# CHIP_tzatziffy_v9.net
KiCad netlist of a schematic drawn in EAGLE
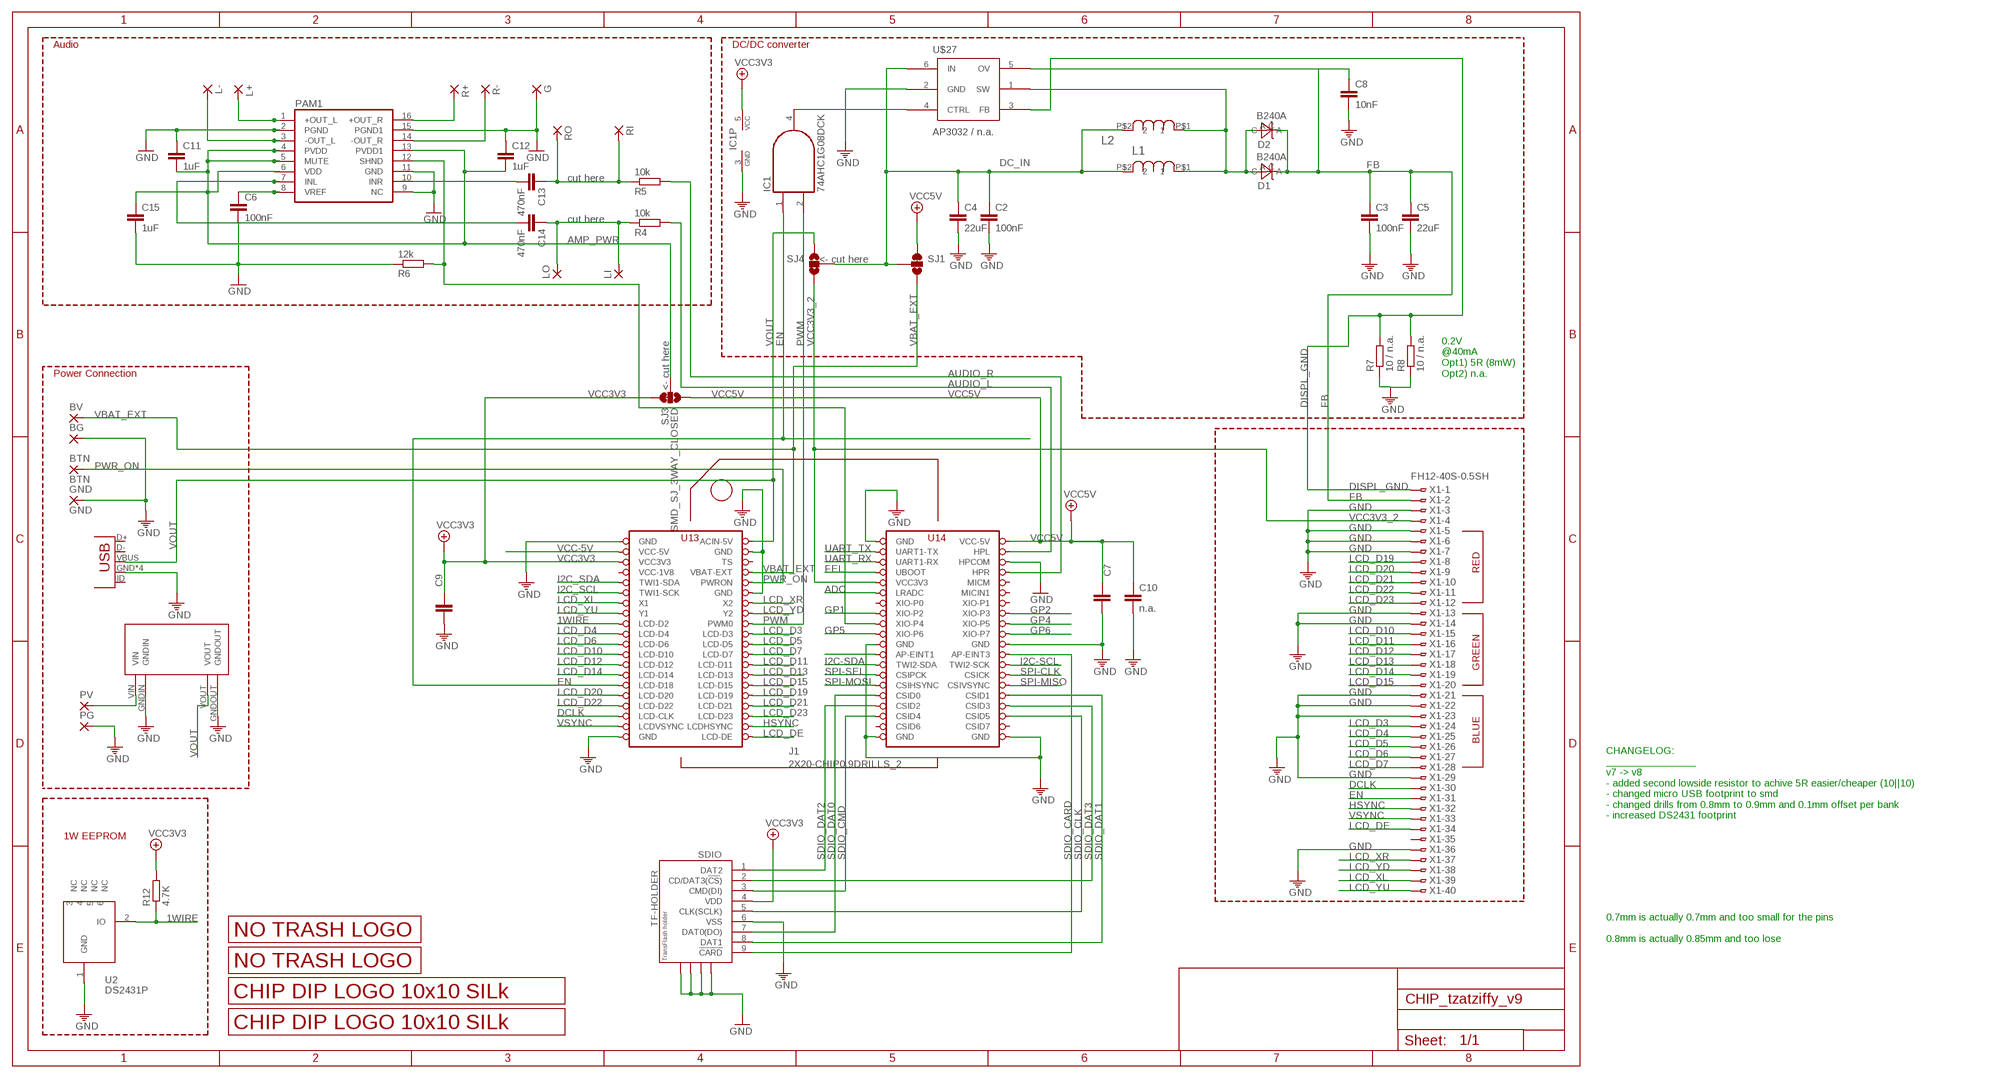
[diagram p0: schematic, sheet 1]

(export (version "E")
  (design (tool "Eeschema 10.0.6"))
  (components
    (comp (ref "BG")
      (value "1,6/0,8")
      (footprint "eagle-import:1,6_0,8")
      (libsource (lib "eagle-import") (part "1,6/0,8"))
    )
    (comp (ref "BTN")
      (value "BTN")
      (footprint "eagle-import:SMD1,27-2,54")
      (libsource (lib "eagle-import") (part "SMD2"))
    )
    (comp (ref "BV")
      (value "1,6/0,8")
      (footprint "eagle-import:1,6_0,8")
      (libsource (lib "eagle-import") (part "1,6/0,8"))
    )
    (comp (ref "C2")
      (value "100nF")
      (footprint "eagle-import:C0805")
      (libsource (lib "eagle-import") (part "C-EUC0805"))
    )
    (comp (ref "C3")
      (value "100nF")
      (footprint "eagle-import:C0805")
      (libsource (lib "eagle-import") (part "C-EUC0805"))
    )
    (comp (ref "C4")
      (value "22uF")
      (footprint "eagle-import:C1206")
      (libsource (lib "eagle-import") (part "C-EUC1206"))
    )
    (comp (ref "C5")
      (value "22uF")
      (footprint "eagle-import:C1206")
      (libsource (lib "eagle-import") (part "C-EUC1206"))
    )
    (comp (ref "C6")
      (value "100nF")
      (footprint "eagle-import:C0805")
      (libsource (lib "eagle-import") (part "C-EUC0805"))
    )
    (comp (ref "C7")
      (value "n.a.")
      (footprint "eagle-import:C0805")
      (libsource (lib "eagle-import") (part "C-EUC0805"))
    )
    (comp (ref "C8")
      (value "10nF")
      (footprint "eagle-import:C0805")
      (libsource (lib "eagle-import") (part "C-EUC0805"))
    )
    (comp (ref "C9")
      (value "n.a.")
      (footprint "eagle-import:C0805")
      (libsource (lib "eagle-import") (part "C-EUC0805"))
    )
    (comp (ref "C10")
      (value "n.a.")
      (footprint "eagle-import:C0805")
      (libsource (lib "eagle-import") (part "C-EUC0805"))
    )
    (comp (ref "C11")
      (value "1uF")
      (footprint "eagle-import:C0805")
      (libsource (lib "eagle-import") (part "C-EUC0805"))
    )
    (comp (ref "C12")
      (value "1uF")
      (footprint "eagle-import:C0805")
      (libsource (lib "eagle-import") (part "C-EUC0805"))
    )
    (comp (ref "C13")
      (value "470nF")
      (footprint "eagle-import:C0805")
      (libsource (lib "eagle-import") (part "C-EUC0805"))
    )
    (comp (ref "C14")
      (value "470nF")
      (footprint "eagle-import:C0805")
      (libsource (lib "eagle-import") (part "C-EUC0805"))
    )
    (comp (ref "C15")
      (value "1uF")
      (footprint "eagle-import:C0805")
      (libsource (lib "eagle-import") (part "C-EUC0805"))
    )
    (comp (ref "D1")
      (value "B240A")
      (footprint "eagle-import:DO-214AC")
      (fields (field (name "MFG") "DIGIKEY") (field (name "VENDOR_PART_NUMBER") "B240A-13-F"))
      (libsource (lib "eagle-import") (part "DIODE_SCHTKY_B240"))
    )
    (comp (ref "D2")
      (value "B240A")
      (footprint "eagle-import:DO-214AC")
      (fields (field (name "MFG") "DIGIKEY") (field (name "VENDOR_PART_NUMBER") "B240A-13-F"))
      (libsource (lib "eagle-import") (part "DIODE_SCHTKY_B240"))
    )
    (comp (ref "G")
      (value "1,6/0,8")
      (footprint "eagle-import:1,6_0,8")
      (libsource (lib "eagle-import") (part "1,6/0,8"))
    )
    (comp (ref "GND")
      (value "GND")
      (footprint "eagle-import:SMD1,27-2,54")
      (libsource (lib "eagle-import") (part "SMD2"))
    )
    (comp (ref "IC1")
      (value "74AHC1G08DCK")
      (footprint "eagle-import:SC70-5")
      (libsource (lib "eagle-import") (part "741G08DCKAHC"))
    )
    (comp (ref "J1")
      (value "2X20-CHIP0.9DRILLS_2")
      (footprint "eagle-import:2X20CHIP_BANK_OFFSET_TH_0.9")
      (libsource (lib "eagle-import") (part "2X20-CHIP0.9DRILLS_2"))
    )
    (comp (ref "JP1")
      (value "USBMICRO_SMD")
      (footprint "eagle-import:USB-B-MICRO-SMD_V03")
      (libsource (lib "eagle-import") (part "USBMICRO_SMD"))
    )
    (comp (ref "L+")
      (value "1,6/0,8")
      (footprint "eagle-import:1,6_0,8")
      (libsource (lib "eagle-import") (part "1,6/0,8"))
    )
    (comp (ref "L-")
      (value "1,6/0,8")
      (footprint "eagle-import:1,6_0,8")
      (libsource (lib "eagle-import") (part "1,6/0,8"))
    )
    (comp (ref "L1")
      (value "SRN6045-100M")
      (footprint "eagle-import:SRN6045")
      (fields (field (name "MFG") "DIGIKEY"))
      (libsource (lib "eagle-import") (part "SRN6045-100M"))
    )
    (comp (ref "L2")
      (value "SRN6045-100M")
      (footprint "eagle-import:SRN6045")
      (fields (field (name "MFG") "DIGIKEY"))
      (libsource (lib "eagle-import") (part "SRN6045-100M"))
    )
    (comp (ref "LI")
      (value "1,6/0,8")
      (footprint "eagle-import:1,6_0,8")
      (libsource (lib "eagle-import") (part "1,6/0,8"))
    )
    (comp (ref "LO")
      (value "1,6/0,8")
      (footprint "eagle-import:1,6_0,8")
      (libsource (lib "eagle-import") (part "1,6/0,8"))
    )
    (comp (ref "PAM1")
      (value "PAM8403")
      (footprint "eagle-import:SOP-16")
      (libsource (lib "eagle-import") (part "PAM8403"))
    )
    (comp (ref "PG")
      (value "1,6/0,8")
      (footprint "eagle-import:1,6_0,8")
      (libsource (lib "eagle-import") (part "1,6/0,8"))
    )
    (comp (ref "PV")
      (value "1,6/0,8")
      (footprint "eagle-import:1,6_0,8")
      (libsource (lib "eagle-import") (part "1,6/0,8"))
    )
    (comp (ref "R+")
      (value "1,6/0,8")
      (footprint "eagle-import:1,6_0,8")
      (libsource (lib "eagle-import") (part "1,6/0,8"))
    )
    (comp (ref "R-")
      (value "1,6/0,8")
      (footprint "eagle-import:1,6_0,8")
      (libsource (lib "eagle-import") (part "1,6/0,8"))
    )
    (comp (ref "R4")
      (value "10k")
      (footprint "eagle-import:R0805")
      (libsource (lib "eagle-import") (part "R-EU_R0805"))
    )
    (comp (ref "R5")
      (value "10k")
      (footprint "eagle-import:R0805")
      (libsource (lib "eagle-import") (part "R-EU_R0805"))
    )
    (comp (ref "R6")
      (value "12k")
      (footprint "eagle-import:R0805")
      (libsource (lib "eagle-import") (part "R-EU_R0805"))
    )
    (comp (ref "R7")
      (value "10 / n.a.")
      (footprint "eagle-import:M0805")
      (libsource (lib "eagle-import") (part "R-EU_M0805"))
    )
    (comp (ref "R8")
      (value "10 / n.a.")
      (footprint "eagle-import:M0805")
      (libsource (lib "eagle-import") (part "R-EU_M0805"))
    )
    (comp (ref "R12")
      (value "4.7K")
      (footprint "eagle-import:M0805")
      (libsource (lib "eagle-import") (part "R-EU_M0805"))
    )
    (comp (ref "RI")
      (value "1,6/0,8")
      (footprint "eagle-import:1,6_0,8")
      (libsource (lib "eagle-import") (part "1,6/0,8"))
    )
    (comp (ref "RO")
      (value "1,6/0,8")
      (footprint "eagle-import:1,6_0,8")
      (libsource (lib "eagle-import") (part "1,6/0,8"))
    )
    (comp (ref "SDIO")
      (value "TF-HOLDER")
      (footprint "eagle-import:TF-PULL")
      (libsource (lib "eagle-import") (part "TF-HOLDER"))
    )
    (comp (ref "SJ1")
      (value "SMD_SJ_3WAY_CLOSED")
      (footprint "eagle-import:SMD_SJ_3WAY_CLOSED")
      (libsource (lib "eagle-import") (part "SMD_SJ_3WAY_CLOSED"))
    )
    (comp (ref "SJ3")
      (value "SMD_SJ_3WAY_CLOSED")
      (footprint "eagle-import:SMD_SJ_3WAY_CLOSED")
      (libsource (lib "eagle-import") (part "SMD_SJ_3WAY_CLOSED"))
    )
    (comp (ref "SJ4")
      (value "SMD_SJ_3WAY_OPENT")
      (footprint "eagle-import:SMD_SJ_3WAY_OPEN")
      (libsource (lib "eagle-import") (part "SMD_SJ_3WAY_OPENT"))
    )
    (comp (ref "U$2")
      (value "LOGO_10X10_SILK")
      (footprint "eagle-import:LOGO2_10X10_SILK")
      (libsource (lib "eagle-import") (part "LOGO_10X10_SILK"))
    )
    (comp (ref "U$3")
      (value "LOGO_NO_TRASHROHS")
      (footprint "eagle-import:LOGO_ROHS_SYM")
      (libsource (lib "eagle-import") (part "LOGO_NO_TRASHROHS"))
    )
    (comp (ref "U$4")
      (value "LOGO_NO_TRASHNO_TRASH")
      (footprint "eagle-import:LOGO_ROHS_NO_TRASH")
      (libsource (lib "eagle-import") (part "LOGO_NO_TRASHNO_TRASH"))
    )
    (comp (ref "U$5")
      (value "LOGO_10X10_SILK")
      (footprint "eagle-import:LOGO2_10X10_SILK")
      (libsource (lib "eagle-import") (part "LOGO_10X10_SILK"))
    )
    (comp (ref "U$10")
      (value "MP1584EN_FRAMELESS")
      (footprint "eagle-import:MP1584EN_FRAMELESS")
      (libsource (lib "eagle-import") (part "MP1584EN_FRAMELESS"))
    )
    (comp (ref "U$27")
      (value "AP3032 / n.a.")
      (footprint "eagle-import:SOT23-6")
      (libsource (lib "eagle-import") (part "AP3032"))
    )
    (comp (ref "U2")
      (value "DS2431P")
      (footprint "eagle-import:TSOC6")
      (fields (field (name "MFG") "DIGIKEY") (field (name "VENDOR_PART_NUMBER") "DS2431P+T&R"))
      (libsource (lib "eagle-import") (part "DS2431P"))
    )
    (comp (ref "X1")
      (value "FH12-40S-0.5SH")
      (footprint "eagle-import:FH12-40S-0.5SH")
      (fields (field (name "MFG") "DIGIKEY") (field (name "VENDOR_PART_NUMBER") "FH12-40S-0.5SH(55)"))
      (libsource (lib "eagle-import") (part "FH12-40S-0.5SH"))
    )
  )
  (nets
    (net (code "1") (name "/1WIRE") (class "Default")
      (node (ref "J1") (pin "LCD-D2") (pinfunction "LCD-D2_LCD-D2") (pintype "passive"))
      (node (ref "R12") (pin "1") (pinfunction "1_1") (pintype "passive"))
      (node (ref "U2") (pin "2") (pinfunction "IO_2") (pintype "bidirectional"))
    )
    (net (code "2") (name "/ADC") (class "Default")
      (node (ref "J1") (pin "LRADC") (pinfunction "LRADC_LRADC") (pintype "passive"))
    )
    (net (code "3") (name "/AMP_PWR") (class "Default")
      (node (ref "C11") (pin "2") (pinfunction "2_2") (pintype "passive"))
      (node (ref "C12") (pin "2") (pinfunction "2_2") (pintype "passive"))
      (node (ref "C15") (pin "1") (pinfunction "1_1") (pintype "passive"))
      (node (ref "PAM1") (pin "13") (pinfunction "PVDD1_13") (pintype "output"))
      (node (ref "PAM1") (pin "4") (pinfunction "PVDD_4") (pintype "input"))
      (node (ref "PAM1") (pin "5") (pinfunction "MUTE_5") (pintype "input"))
      (node (ref "PAM1") (pin "6") (pinfunction "VDD_6") (pintype "input"))
      (node (ref "SJ3") (pin "2") (pinfunction "2_2") (pintype "passive"))
    )
    (net (code "4") (name "/AUDIO_L") (class "Default")
      (node (ref "J1") (pin "HPL") (pinfunction "HPL_HPL") (pintype "passive"))
      (node (ref "R4") (pin "2") (pinfunction "2_2") (pintype "passive"))
    )
    (net (code "5") (name "/AUDIO_R") (class "Default")
      (node (ref "J1") (pin "HPR") (pinfunction "HPR_HPR") (pintype "passive"))
      (node (ref "R5") (pin "2") (pinfunction "2_2") (pintype "passive"))
    )
    (net (code "6") (name "/DCLK") (class "Default")
      (node (ref "J1") (pin "LCD-CLK") (pinfunction "LCD-CLK_LCD-CLK") (pintype "passive"))
      (node (ref "X1") (pin "30") (pinfunction "1_30") (pintype "passive"))
    )
    (net (code "7") (name "/DC_IN") (class "Default")
      (node (ref "C2") (pin "1") (pinfunction "1_1") (pintype "passive"))
      (node (ref "C4") (pin "1") (pinfunction "1_1") (pintype "passive"))
      (node (ref "L1") (pin "P$2") (pinfunction "2_P$2") (pintype "passive"))
      (node (ref "L2") (pin "P$2") (pinfunction "2_P$2") (pintype "passive"))
      (node (ref "SJ1") (pin "2") (pinfunction "2_2") (pintype "passive"))
      (node (ref "SJ4") (pin "2") (pinfunction "2_2") (pintype "passive"))
      (node (ref "U$27") (pin "6") (pinfunction "IN_6") (pintype "power_in"))
    )
    (net (code "8") (name "/DISPL_GND") (class "Default")
      (node (ref "R7") (pin "2") (pinfunction "2_2") (pintype "passive"))
      (node (ref "R8") (pin "2") (pinfunction "2_2") (pintype "passive"))
      (node (ref "U$27") (pin "3") (pinfunction "FB_3") (pintype "passive"))
      (node (ref "X1") (pin "1") (pinfunction "1_1") (pintype "passive"))
    )
    (net (code "9") (name "/EN") (class "Default")
      (node (ref "IC1") (pin "1") (pinfunction "I0_1") (pintype "input"))
      (node (ref "J1") (pin "LCD-D18") (pinfunction "LCD-D18_LCD-D18") (pintype "passive"))
      (node (ref "X1") (pin "31") (pinfunction "1_31") (pintype "passive"))
    )
    (net (code "10") (name "/FB") (class "Default")
      (node (ref "C3") (pin "1") (pinfunction "1_1") (pintype "passive"))
      (node (ref "C5") (pin "1") (pinfunction "1_1") (pintype "passive"))
      (node (ref "C8") (pin "1") (pinfunction "1_1") (pintype "passive"))
      (node (ref "D1") (pin "C") (pinfunction "C_C") (pintype "bidirectional"))
      (node (ref "D2") (pin "C") (pinfunction "C_C") (pintype "bidirectional"))
      (node (ref "U$27") (pin "5") (pinfunction "OV_5") (pintype "power_in"))
      (node (ref "X1") (pin "2") (pinfunction "1_2") (pintype "passive"))
    )
    (net (code "11") (name "/FEL") (class "Default")
      (node (ref "J1") (pin "FEL") (pinfunction "UBOOT_FEL") (pintype "passive"))
    )
    (net (code "12") (name "/GP1") (class "Default")
      (node (ref "J1") (pin "XIO-P2") (pinfunction "XIO-P2_XIO-P2") (pintype "passive"))
    )
    (net (code "13") (name "/GP2") (class "Default")
      (node (ref "J1") (pin "XIO-P3") (pinfunction "XIO-P3_XIO-P3") (pintype "passive"))
    )
    (net (code "14") (name "/GP4") (class "Default")
      (node (ref "J1") (pin "XIO-P5") (pinfunction "XIO-P5_XIO-P5") (pintype "passive"))
    )
    (net (code "15") (name "/GP5") (class "Default")
      (node (ref "J1") (pin "XIO-P6") (pinfunction "XIO-P6_XIO-P6") (pintype "passive"))
    )
    (net (code "16") (name "/GP6") (class "Default")
      (node (ref "J1") (pin "XIO-P7") (pinfunction "XIO-P7_XIO-P7") (pintype "passive"))
    )
    (net (code "17") (name "/HSYNC") (class "Default")
      (node (ref "J1") (pin "LCD-HSYNC") (pinfunction "LCDHSYNC_LCD-HSYNC") (pintype "passive"))
      (node (ref "X1") (pin "32") (pinfunction "1_32") (pintype "passive"))
    )
    (net (code "18") (name "/I2C-SCL") (class "Default")
      (node (ref "J1") (pin "TWI2-SCK") (pinfunction "TWI2-SCK_TWI2-SCK") (pintype "passive"))
    )
    (net (code "19") (name "/I2C-SDA") (class "Default")
      (node (ref "J1") (pin "TWI2-SDA") (pinfunction "TWI2-SDA_TWI2-SDA") (pintype "passive"))
    )
    (net (code "20") (name "/I2C_SCL") (class "Default")
      (node (ref "J1") (pin "TWI1-SCK") (pinfunction "TWI1-SCK_TWI1-SCK") (pintype "passive"))
    )
    (net (code "21") (name "/I2C_SDA") (class "Default")
      (node (ref "J1") (pin "TWI1-SDA") (pinfunction "TWI1-SDA_TWI1-SDA") (pintype "passive"))
    )
    (net (code "22") (name "/LCD_D3") (class "Default")
      (node (ref "J1") (pin "LCD-D3") (pinfunction "LCD-D3_LCD-D3") (pintype "passive"))
      (node (ref "X1") (pin "24") (pinfunction "1_24") (pintype "passive"))
    )
    (net (code "23") (name "/LCD_D4") (class "Default")
      (node (ref "J1") (pin "LCD-D4") (pinfunction "LCD-D4_LCD-D4") (pintype "passive"))
      (node (ref "X1") (pin "25") (pinfunction "1_25") (pintype "passive"))
    )
    (net (code "24") (name "/LCD_D5") (class "Default")
      (node (ref "J1") (pin "LCD-D5") (pinfunction "LCD-D5_LCD-D5") (pintype "passive"))
      (node (ref "X1") (pin "26") (pinfunction "1_26") (pintype "passive"))
    )
    (net (code "25") (name "/LCD_D6") (class "Default")
      (node (ref "J1") (pin "LCD-D6") (pinfunction "LCD-D6_LCD-D6") (pintype "passive"))
      (node (ref "X1") (pin "27") (pinfunction "1_27") (pintype "passive"))
    )
    (net (code "26") (name "/LCD_D7") (class "Default")
      (node (ref "J1") (pin "LCD-D7") (pinfunction "LCD-D7_LCD-D7") (pintype "passive"))
      (node (ref "X1") (pin "28") (pinfunction "1_28") (pintype "passive"))
    )
    (net (code "27") (name "/LCD_D10") (class "Default")
      (node (ref "J1") (pin "LCD-D10") (pinfunction "LCD-D10_LCD-D10") (pintype "passive"))
      (node (ref "X1") (pin "15") (pinfunction "1_15") (pintype "passive"))
    )
    (net (code "28") (name "/LCD_D11") (class "Default")
      (node (ref "J1") (pin "LCD-D11") (pinfunction "LCD-D11_LCD-D11") (pintype "passive"))
      (node (ref "X1") (pin "16") (pinfunction "1_16") (pintype "passive"))
    )
    (net (code "29") (name "/LCD_D12") (class "Default")
      (node (ref "J1") (pin "LCD-D12") (pinfunction "LCD-D12_LCD-D12") (pintype "passive"))
      (node (ref "X1") (pin "17") (pinfunction "1_17") (pintype "passive"))
    )
    (net (code "30") (name "/LCD_D13") (class "Default")
      (node (ref "J1") (pin "LCD-D13") (pinfunction "LCD-D13_LCD-D13") (pintype "passive"))
      (node (ref "X1") (pin "18") (pinfunction "1_18") (pintype "passive"))
    )
    (net (code "31") (name "/LCD_D14") (class "Default")
      (node (ref "J1") (pin "LCD-D14") (pinfunction "LCD-D14_LCD-D14") (pintype "passive"))
      (node (ref "X1") (pin "19") (pinfunction "1_19") (pintype "passive"))
    )
    (net (code "32") (name "/LCD_D15") (class "Default")
      (node (ref "J1") (pin "LCD-D15") (pinfunction "LCD-D15_LCD-D15") (pintype "passive"))
      (node (ref "X1") (pin "20") (pinfunction "1_20") (pintype "passive"))
    )
    (net (code "33") (name "/LCD_D19") (class "Default")
      (node (ref "J1") (pin "LCD-D19") (pinfunction "LCD-D19_LCD-D19") (pintype "passive"))
      (node (ref "X1") (pin "8") (pinfunction "1_8") (pintype "passive"))
    )
    (net (code "34") (name "/LCD_D20") (class "Default")
      (node (ref "J1") (pin "LCD-D20") (pinfunction "LCD-D20_LCD-D20") (pintype "passive"))
      (node (ref "X1") (pin "9") (pinfunction "1_9") (pintype "passive"))
    )
    (net (code "35") (name "/LCD_D21") (class "Default")
      (node (ref "J1") (pin "LCD-D21") (pinfunction "LCD-D21_LCD-D21") (pintype "passive"))
      (node (ref "X1") (pin "10") (pinfunction "1_10") (pintype "passive"))
    )
    (net (code "36") (name "/LCD_D22") (class "Default")
      (node (ref "J1") (pin "LCD-D22") (pinfunction "LCD-D22_LCD-D22") (pintype "passive"))
      (node (ref "X1") (pin "11") (pinfunction "1_11") (pintype "passive"))
    )
    (net (code "37") (name "/LCD_D23") (class "Default")
      (node (ref "J1") (pin "LCD-D23") (pinfunction "LCD-D23_LCD-D23") (pintype "passive"))
      (node (ref "X1") (pin "12") (pinfunction "1_12") (pintype "passive"))
    )
    (net (code "38") (name "/LCD_DE") (class "Default")
      (node (ref "J1") (pin "LCD-DE") (pinfunction "LCD-DE_LCD-DE") (pintype "passive"))
      (node (ref "X1") (pin "34") (pinfunction "1_34") (pintype "passive"))
    )
    (net (code "39") (name "/LCD_XL") (class "Default")
      (node (ref "J1") (pin "X1") (pinfunction "X1_X1") (pintype "passive"))
      (node (ref "X1") (pin "39") (pinfunction "1_39") (pintype "passive"))
    )
    (net (code "40") (name "/LCD_XR") (class "Default")
      (node (ref "J1") (pin "X2") (pinfunction "X2_X2") (pintype "passive"))
      (node (ref "X1") (pin "37") (pinfunction "1_37") (pintype "passive"))
    )
    (net (code "41") (name "/LCD_YD") (class "Default")
      (node (ref "J1") (pin "Y2") (pinfunction "Y2_Y2") (pintype "passive"))
      (node (ref "X1") (pin "38") (pinfunction "1_38") (pintype "passive"))
    )
    (net (code "42") (name "/LCD_YU") (class "Default")
      (node (ref "J1") (pin "Y1") (pinfunction "Y1_Y1") (pintype "passive"))
      (node (ref "X1") (pin "40") (pinfunction "1_40") (pintype "passive"))
    )
    (net (code "43") (name "/PWM") (class "Default")
      (node (ref "IC1") (pin "2") (pinfunction "I1_2") (pintype "input"))
      (node (ref "J1") (pin "PWM0") (pinfunction "PWM0_PWM0") (pintype "passive"))
    )
    (net (code "44") (name "/PWR_ON") (class "Default")
      (node (ref "BTN") (pin "1") (pinfunction "P_1") (pintype "passive"))
      (node (ref "J1") (pin "PWRON") (pinfunction "PWRON_PWRON") (pintype "passive"))
    )
    (net (code "45") (name "/SDIO_CARD") (class "Default")
      (node (ref "J1") (pin "AP-EINT3") (pinfunction "AP-EINT3_AP-EINT3") (pintype "passive"))
      (node (ref "SDIO") (pin "9") (pinfunction "~{CARD}_9") (pintype "passive"))
    )
    (net (code "46") (name "/SDIO_CLK") (class "Default")
      (node (ref "J1") (pin "CSID5") (pinfunction "CSID5_CSID5") (pintype "passive"))
      (node (ref "SDIO") (pin "5") (pinfunction "CLK(SCLK)_5") (pintype "input"))
    )
    (net (code "47") (name "/SDIO_CMD") (class "Default")
      (node (ref "J1") (pin "CSID4") (pinfunction "CSID4_CSID4") (pintype "passive"))
      (node (ref "SDIO") (pin "3") (pinfunction "CMD(DI)_3") (pintype "bidirectional"))
    )
    (net (code "48") (name "/SDIO_DAT0") (class "Default")
      (node (ref "J1") (pin "CSID0") (pinfunction "CSID0_CSID0") (pintype "passive"))
      (node (ref "SDIO") (pin "7") (pinfunction "DAT0(DO)_7") (pintype "bidirectional"))
    )
    (net (code "49") (name "/SDIO_DAT1") (class "Default")
      (node (ref "J1") (pin "CSID1") (pinfunction "CSID1_CSID1") (pintype "passive"))
      (node (ref "SDIO") (pin "8") (pinfunction "DAT1_8") (pintype "bidirectional"))
    )
    (net (code "50") (name "/SDIO_DAT2") (class "Default")
      (node (ref "J1") (pin "CSID2") (pinfunction "CSID2_CSID2") (pintype "passive"))
      (node (ref "SDIO") (pin "1") (pinfunction "DAT2_1") (pintype "bidirectional"))
    )
    (net (code "51") (name "/SDIO_DAT3") (class "Default")
      (node (ref "J1") (pin "CSID3") (pinfunction "CSID3_CSID3") (pintype "passive"))
      (node (ref "SDIO") (pin "2") (pinfunction "CD/DAT3(~{CS})_2") (pintype "bidirectional"))
    )
    (net (code "52") (name "/SPI-CLK") (class "Default")
      (node (ref "J1") (pin "CSICK") (pinfunction "CSICK_CSICK") (pintype "passive"))
    )
    (net (code "53") (name "/SPI-MISO") (class "Default")
      (node (ref "J1") (pin "CSIVSYNC") (pinfunction "CSIVSYNC_CSIVSYNC") (pintype "passive"))
    )
    (net (code "54") (name "/SPI-MOSI") (class "Default")
      (node (ref "J1") (pin "CSIHSYNC") (pinfunction "CSIHSYNC_CSIHSYNC") (pintype "passive"))
    )
    (net (code "55") (name "/SPI-SEL") (class "Default")
      (node (ref "J1") (pin "CSIPCK") (pinfunction "CSIPCK_CSIPCK") (pintype "passive"))
    )
    (net (code "56") (name "/UART_RX") (class "Default")
      (node (ref "J1") (pin "UART1-RX") (pinfunction "UART1-RX_UART1-RX") (pintype "passive"))
    )
    (net (code "57") (name "/UART_TX") (class "Default")
      (node (ref "J1") (pin "UART1-TX") (pinfunction "UART1-TX_UART1-TX") (pintype "passive"))
    )
    (net (code "58") (name "/VBAT_EXT") (class "Default")
      (node (ref "BV") (pin "1") (pinfunction "P_1") (pintype "passive"))
      (node (ref "J1") (pin "BAT") (pinfunction "VBAT-EXT_BAT") (pintype "passive"))
      (node (ref "SJ1") (pin "3") (pinfunction "3_3") (pintype "passive"))
    )
    (net (code "59") (name "/VCC-1V8") (class "Default")
      (node (ref "J1") (pin "VCC1V8") (pinfunction "VCC-1V8_VCC1V8") (pintype "power_in"))
    )
    (net (code "60") (name "/VCC-5V") (class "Default")
      (node (ref "J1") (pin "VCC5V@0") (pinfunction "VCC-5V_VCC5V@0") (pintype "power_in"))
    )
    (net (code "61") (name "/VCC3V3_2") (class "Default")
      (node (ref "J1") (pin "VCC3V3@1") (pinfunction "VCC3V3_VCC3V3@1") (pintype "power_in"))
      (node (ref "SJ4") (pin "3") (pinfunction "3_3") (pintype "passive"))
      (node (ref "X1") (pin "4") (pinfunction "1_4") (pintype "passive"))
    )
    (net (code "62") (name "/VOUT") (class "Default")
      (node (ref "J1") (pin "CHG-IN") (pinfunction "ACIN-5V_CHG-IN") (pintype "passive"))
      (node (ref "JP1") (pin "VBUS") (pinfunction "VBUS_VBUS") (pintype "bidirectional"))
      (node (ref "SJ4") (pin "1") (pinfunction "1_1") (pintype "passive"))
      (node (ref "U$10") (pin "VOUT") (pinfunction "VOUT_VOUT") (pintype "power_in"))
    )
    (net (code "63") (name "/VSYNC") (class "Default")
      (node (ref "J1") (pin "LCD-VSYNC") (pinfunction "LCDVSYNC_LCD-VSYNC") (pintype "passive"))
      (node (ref "X1") (pin "33") (pinfunction "1_33") (pintype "passive"))
    )
    (net (code "64") (name "GND") (class "Default")
      (node (ref "BG") (pin "1") (pinfunction "P_1") (pintype "passive"))
      (node (ref "C10") (pin "2") (pinfunction "2_2") (pintype "passive"))
      (node (ref "C11") (pin "1") (pinfunction "1_1") (pintype "passive"))
      (node (ref "C12") (pin "1") (pinfunction "1_1") (pintype "passive"))
      (node (ref "C15") (pin "2") (pinfunction "2_2") (pintype "passive"))
      (node (ref "C2") (pin "2") (pinfunction "2_2") (pintype "passive"))
      (node (ref "C3") (pin "2") (pinfunction "2_2") (pintype "passive"))
      (node (ref "C4") (pin "2") (pinfunction "2_2") (pintype "passive"))
      (node (ref "C5") (pin "2") (pinfunction "2_2") (pintype "passive"))
      (node (ref "C6") (pin "2") (pinfunction "2_2") (pintype "passive"))
      (node (ref "C7") (pin "2") (pinfunction "2_2") (pintype "passive"))
      (node (ref "C8") (pin "2") (pinfunction "2_2") (pintype "passive"))
      (node (ref "C9") (pin "2") (pinfunction "2_2") (pintype "passive"))
      (node (ref "G") (pin "1") (pinfunction "P_1") (pintype "passive"))
      (node (ref "GND") (pin "1") (pinfunction "P_1") (pintype "passive"))
      (node (ref "IC1") (pin "3") (pinfunction "GND_3") (pintype "power_in"))
      (node (ref "J1") (pin "GND@1") (pinfunction "GND_GND@1") (pintype "power_in"))
      (node (ref "J1") (pin "GND@10") (pinfunction "GND_GND@10") (pintype "power_in"))
      (node (ref "J1") (pin "GND@2") (pinfunction "GND_GND@2") (pintype "power_in"))
      (node (ref "J1") (pin "GND@3") (pinfunction "GND_GND@3") (pintype "power_in"))
      (node (ref "J1") (pin "GND@4") (pinfunction "GND_GND@4") (pintype "power_in"))
      (node (ref "J1") (pin "GND@5") (pinfunction "GND_GND@5") (pintype "power_in"))
      (node (ref "J1") (pin "GND@6") (pinfunction "GND_GND@6") (pintype "power_in"))
      (node (ref "J1") (pin "GND@7") (pinfunction "GND_GND@7") (pintype "power_in"))
      (node (ref "J1") (pin "GND@8") (pinfunction "GND_GND@8") (pintype "power_in"))
      (node (ref "J1") (pin "HPCOM") (pinfunction "HPCOM_HPCOM") (pintype "passive"))
      (node (ref "JP1") (pin "GND") (pinfunction "GND_GND") (pintype "bidirectional"))
      (node (ref "JP1") (pin "SHIELD1") (pinfunction "GND_SHIELD1") (pintype "bidirectional"))
      (node (ref "JP1") (pin "SHIELD2") (pinfunction "GND_SHIELD2") (pintype "bidirectional"))
      (node (ref "JP1") (pin "SHIELD3") (pinfunction "GND_SHIELD3") (pintype "bidirectional"))
      (node (ref "PAM1") (pin "11") (pinfunction "GND_11") (pintype "output"))
      (node (ref "PAM1") (pin "15") (pinfunction "PGND1_15") (pintype "output"))
      (node (ref "PAM1") (pin "2") (pinfunction "PGND_2") (pintype "input"))
      (node (ref "PAM1") (pin "9") (pinfunction "NC_9") (pintype "output"))
      (node (ref "PG") (pin "1") (pinfunction "P_1") (pintype "passive"))
      (node (ref "R6") (pin "1") (pinfunction "1_1") (pintype "passive"))
      (node (ref "R7") (pin "1") (pinfunction "1_1") (pintype "passive"))
      (node (ref "R8") (pin "1") (pinfunction "1_1") (pintype "passive"))
      (node (ref "SDIO") (pin "6") (pinfunction "VSS_6") (pintype "power_in"))
      (node (ref "SDIO") (pin "S1") (pinfunction "S1_S1") (pintype "passive"))
      (node (ref "SDIO") (pin "S2") (pinfunction "S2_S2") (pintype "passive"))
      (node (ref "SDIO") (pin "S3") (pinfunction "S3_S3") (pintype "passive"))
      (node (ref "SDIO") (pin "S4") (pinfunction "S4_S4") (pintype "passive"))
      (node (ref "U$10") (pin "GNDIN") (pinfunction "GNDIN_GNDIN") (pintype "power_in"))
      (node (ref "U$10") (pin "GNDOUT") (pinfunction "GNDOUT_GNDOUT") (pintype "power_in"))
      (node (ref "U$27") (pin "2") (pinfunction "GND_2") (pintype "power_in"))
      (node (ref "U2") (pin "1") (pinfunction "GND_1") (pintype "bidirectional"))
      (node (ref "X1") (pin "13") (pinfunction "1_13") (pintype "passive"))
      (node (ref "X1") (pin "14") (pinfunction "1_14") (pintype "passive"))
      (node (ref "X1") (pin "21") (pinfunction "1_21") (pintype "passive"))
      (node (ref "X1") (pin "22") (pinfunction "1_22") (pintype "passive"))
      (node (ref "X1") (pin "23") (pinfunction "1_23") (pintype "passive"))
      (node (ref "X1") (pin "29") (pinfunction "1_29") (pintype "passive"))
      (node (ref "X1") (pin "3") (pinfunction "1_3") (pintype "passive"))
      (node (ref "X1") (pin "36") (pinfunction "1_36") (pintype "passive"))
      (node (ref "X1") (pin "5") (pinfunction "1_5") (pintype "passive"))
      (node (ref "X1") (pin "6") (pinfunction "1_6") (pintype "passive"))
      (node (ref "X1") (pin "7") (pinfunction "1_7") (pintype "passive"))
    )
    (net (code "65") (name "Net-(IC1A-O)") (class "Default")
      (node (ref "IC1") (pin "4") (pinfunction "O_4") (pintype "output"))
      (node (ref "U$27") (pin "4") (pinfunction "CTRL_4") (pintype "input"))
    )
    (net (code "66") (name "Net-(L+-P)") (class "Default")
      (node (ref "L+") (pin "1") (pinfunction "P_1") (pintype "passive"))
      (node (ref "PAM1") (pin "1") (pinfunction "+OUT_L_1") (pintype "input"))
    )
    (net (code "67") (name "Net-(L--P)") (class "Default")
      (node (ref "L-") (pin "1") (pinfunction "P_1") (pintype "passive"))
      (node (ref "PAM1") (pin "3") (pinfunction "-OUT_L_3") (pintype "input"))
    )
    (net (code "68") (name "Net-(L1-1)") (class "Default")
      (node (ref "D1") (pin "A") (pinfunction "A_A") (pintype "bidirectional"))
      (node (ref "D2") (pin "A") (pinfunction "A_A") (pintype "bidirectional"))
      (node (ref "L1") (pin "P$1") (pinfunction "1_P$1") (pintype "passive"))
      (node (ref "L2") (pin "P$1") (pinfunction "1_P$1") (pintype "passive"))
      (node (ref "U$27") (pin "1") (pinfunction "SW_1") (pintype "power_in"))
    )
    (net (code "69") (name "Net-(LI-P)") (class "Default")
      (node (ref "C14") (pin "1") (pinfunction "1_1") (pintype "passive"))
      (node (ref "LI") (pin "1") (pinfunction "P_1") (pintype "passive"))
      (node (ref "LO") (pin "1") (pinfunction "P_1") (pintype "passive"))
      (node (ref "R4") (pin "1") (pinfunction "1_1") (pintype "passive"))
    )
    (net (code "70") (name "Net-(PAM1-+OUT_R)") (class "Default")
      (node (ref "PAM1") (pin "16") (pinfunction "+OUT_R_16") (pintype "output"))
      (node (ref "R+") (pin "1") (pinfunction "P_1") (pintype "passive"))
    )
    (net (code "71") (name "Net-(PAM1--OUT_R)") (class "Default")
      (node (ref "PAM1") (pin "14") (pinfunction "-OUT_R_14") (pintype "output"))
      (node (ref "R-") (pin "1") (pinfunction "P_1") (pintype "passive"))
    )
    (net (code "72") (name "Net-(PAM1-INL)") (class "Default")
      (node (ref "C14") (pin "2") (pinfunction "2_2") (pintype "passive"))
      (node (ref "PAM1") (pin "7") (pinfunction "INL_7") (pintype "input"))
    )
    (net (code "73") (name "Net-(PAM1-INR)") (class "Default")
      (node (ref "C13") (pin "2") (pinfunction "2_2") (pintype "passive"))
      (node (ref "PAM1") (pin "10") (pinfunction "INR_10") (pintype "output"))
    )
    (net (code "74") (name "Net-(PAM1-SHND)") (class "Default")
      (node (ref "J1") (pin "XIO-P4") (pinfunction "XIO-P4_XIO-P4") (pintype "passive"))
      (node (ref "PAM1") (pin "12") (pinfunction "SHND_12") (pintype "output"))
      (node (ref "R6") (pin "2") (pinfunction "2_2") (pintype "passive"))
    )
    (net (code "75") (name "Net-(PAM1-VREF)") (class "Default")
      (node (ref "C6") (pin "1") (pinfunction "1_1") (pintype "passive"))
      (node (ref "PAM1") (pin "8") (pinfunction "VREF_8") (pintype "input"))
    )
    (net (code "76") (name "Net-(PV-P)") (class "Default")
      (node (ref "PV") (pin "1") (pinfunction "P_1") (pintype "passive"))
      (node (ref "U$10") (pin "VIN") (pinfunction "VIN_VIN") (pintype "power_in"))
    )
    (net (code "77") (name "Net-(RI-P)") (class "Default")
      (node (ref "C13") (pin "1") (pinfunction "1_1") (pintype "passive"))
      (node (ref "R5") (pin "1") (pinfunction "1_1") (pintype "passive"))
      (node (ref "RI") (pin "1") (pinfunction "P_1") (pintype "passive"))
      (node (ref "RO") (pin "1") (pinfunction "P_1") (pintype "passive"))
    )
    (net (code "78") (name "VCC3V3") (class "Default")
      (node (ref "C9") (pin "1") (pinfunction "1_1") (pintype "passive"))
      (node (ref "IC1") (pin "5") (pinfunction "VCC_5") (pintype "power_in"))
      (node (ref "J1") (pin "VCC3V3") (pinfunction "VCC3V3_VCC3V3") (pintype "power_in"))
      (node (ref "R12") (pin "2") (pinfunction "2_2") (pintype "passive"))
      (node (ref "SDIO") (pin "4") (pinfunction "VDD_4") (pintype "power_in"))
      (node (ref "SJ3") (pin "1") (pinfunction "1_1") (pintype "passive"))
    )
    (net (code "79") (name "VCC5V") (class "Default")
      (node (ref "C10") (pin "1") (pinfunction "1_1") (pintype "passive"))
      (node (ref "C7") (pin "1") (pinfunction "1_1") (pintype "passive"))
      (node (ref "J1") (pin "VCC5V@1") (pinfunction "VCC-5V_VCC5V@1") (pintype "power_in"))
      (node (ref "SJ1") (pin "1") (pinfunction "1_1") (pintype "passive"))
      (node (ref "SJ3") (pin "3") (pinfunction "3_3") (pintype "passive"))
    )
    (net (code "80") (name "unconnected-(J1-PadAP-EINT1)") (class "Default")
      (node (ref "J1") (pin "AP-EINT1") (pinfunction "AP-EINT1_AP-EINT1") (pintype "passive"))
    )
    (net (code "81") (name "unconnected-(J1-PadCSID6)") (class "Default")
      (node (ref "J1") (pin "CSID6") (pinfunction "CSID6_CSID6") (pintype "passive"))
    )
    (net (code "82") (name "unconnected-(J1-PadCSID7)") (class "Default")
      (node (ref "J1") (pin "CSID7") (pinfunction "CSID7_CSID7") (pintype "passive"))
    )
    (net (code "83") (name "unconnected-(J1-PadMICIN1)") (class "Default")
      (node (ref "J1") (pin "MICIN1") (pinfunction "MICIN1_MICIN1") (pintype "passive"))
    )
    (net (code "84") (name "unconnected-(J1-PadMICM)") (class "Default")
      (node (ref "J1") (pin "MICM") (pinfunction "MICM_MICM") (pintype "passive"))
    )
    (net (code "85") (name "unconnected-(J1-PadTS)") (class "Default")
      (node (ref "J1") (pin "TS") (pinfunction "TS_TS") (pintype "passive"))
    )
    (net (code "86") (name "unconnected-(J1-PadXIO-P0)") (class "Default")
      (node (ref "J1") (pin "XIO-P0") (pinfunction "XIO-P0_XIO-P0") (pintype "passive"))
    )
    (net (code "87") (name "unconnected-(J1-PadXIO-P1)") (class "Default")
      (node (ref "J1") (pin "XIO-P1") (pinfunction "XIO-P1_XIO-P1") (pintype "passive"))
    )
    (net (code "88") (name "unconnected-(JP1-PadD+)") (class "Default")
      (node (ref "JP1") (pin "D+") (pinfunction "D+_D+") (pintype "bidirectional"))
    )
    (net (code "89") (name "unconnected-(JP1-PadD-)") (class "Default")
      (node (ref "JP1") (pin "D-") (pinfunction "D-_D-") (pintype "bidirectional"))
    )
    (net (code "90") (name "unconnected-(JP1-PadID)") (class "Default")
      (node (ref "JP1") (pin "ID") (pinfunction "ID_ID") (pintype "bidirectional"))
    )
    (net (code "91") (name "unconnected-(U2-NC-Pad3)") (class "Default")
      (node (ref "U2") (pin "3") (pinfunction "NC_3") (pintype "bidirectional"))
    )
    (net (code "92") (name "unconnected-(U2-NC-Pad4)") (class "Default")
      (node (ref "U2") (pin "4") (pinfunction "NC_4") (pintype "bidirectional"))
    )
    (net (code "93") (name "unconnected-(U2-NC-Pad5)") (class "Default")
      (node (ref "U2") (pin "5") (pinfunction "NC_5") (pintype "bidirectional"))
    )
    (net (code "94") (name "unconnected-(U2-NC-Pad6)") (class "Default")
      (node (ref "U2") (pin "6") (pinfunction "NC_6") (pintype "bidirectional"))
    )
    (net (code "95") (name "unconnected-(X1AC-1-Pad35)") (class "Default")
      (node (ref "X1") (pin "35") (pinfunction "1_35") (pintype "passive"))
    )
  )
)
